# 4H-Charlieplex84.net
KiCad netlist of a schematic drawn in EAGLE
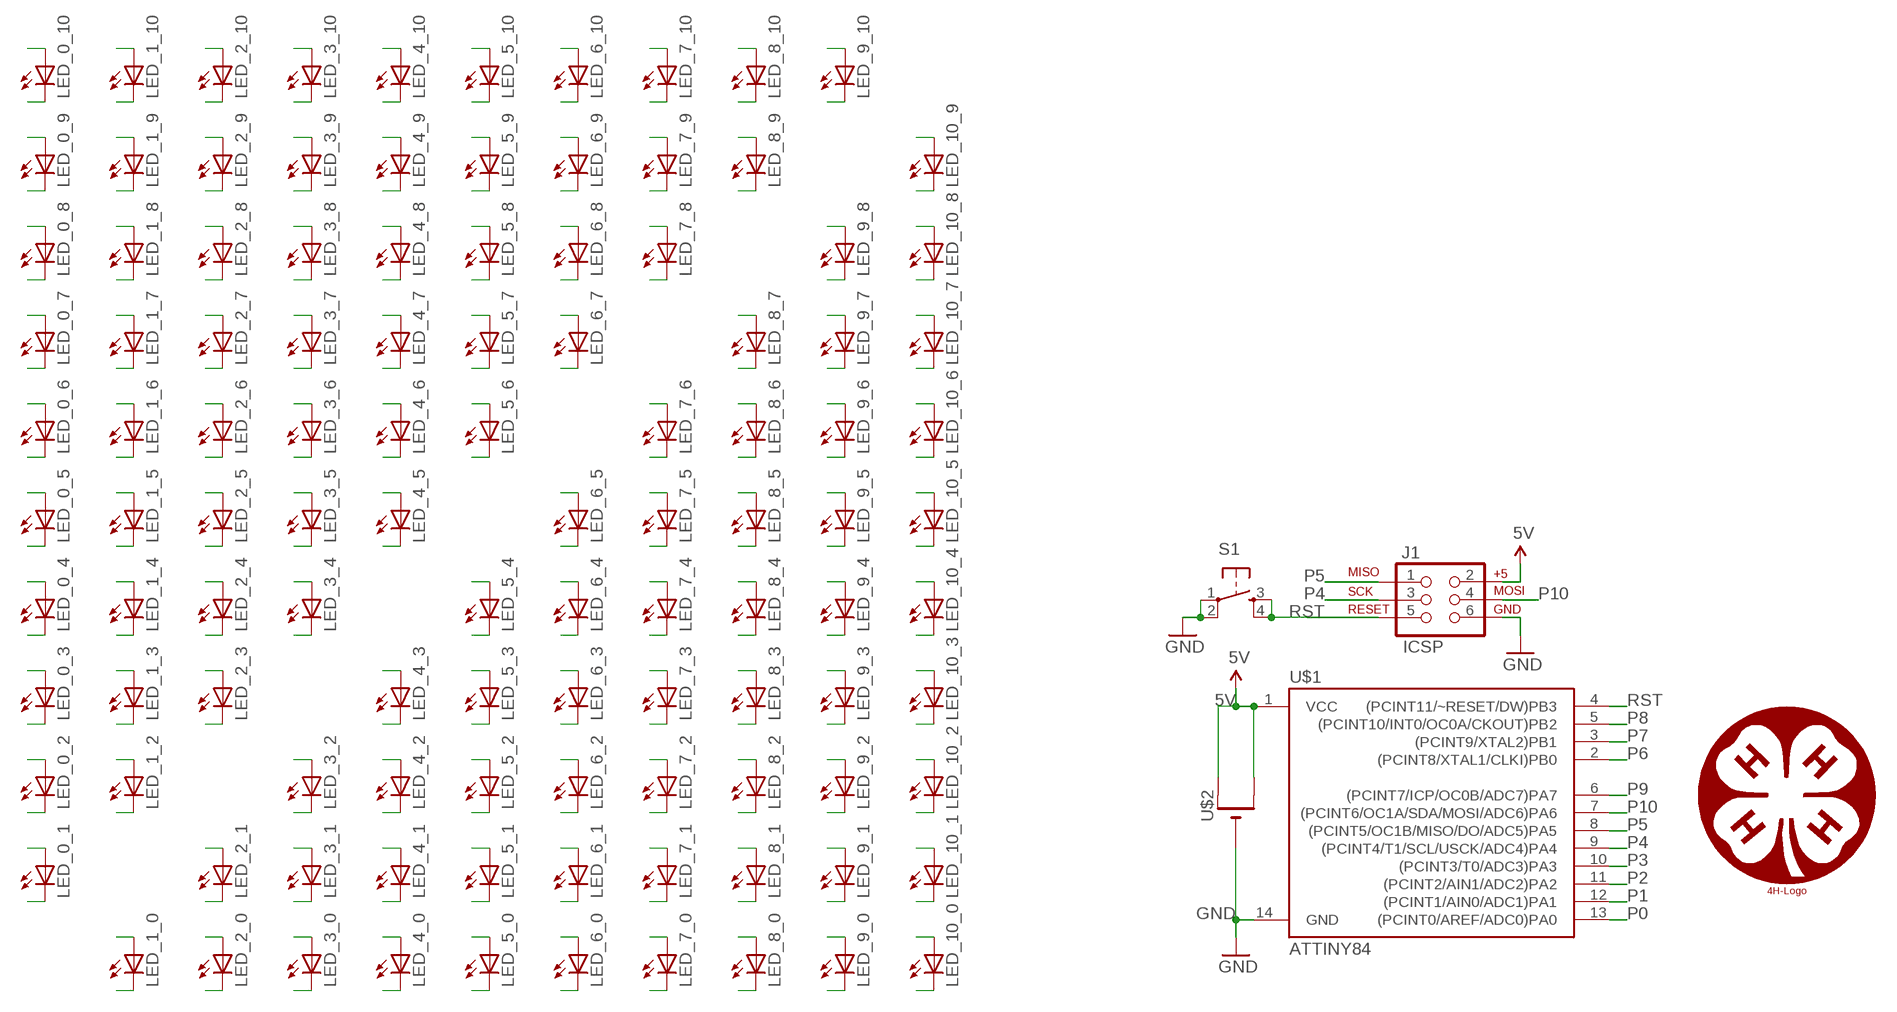
[diagram p0: schematic, sheet 1]

(export (version "E")
  (design (tool "Eeschema 10.0.6"))
  (components
    (comp (ref "J1")
      (value "ICSP")
      (footprint "eagle-import:2X3-NS")
      (libsource (lib "eagle-import") (part "AVR_SPI_PRG_6LABELED"))
    )
    (comp (ref "LED_0_1")
      (value "LEDOVAL")
      (footprint "eagle-import:LED-OVAL")
      (libsource (lib "eagle-import") (part "LEDOVAL"))
    )
    (comp (ref "LED_0_2")
      (value "LEDOVAL")
      (footprint "eagle-import:LED-OVAL")
      (libsource (lib "eagle-import") (part "LEDOVAL"))
    )
    (comp (ref "LED_0_3")
      (value "LEDOVAL")
      (footprint "eagle-import:LED-OVAL")
      (libsource (lib "eagle-import") (part "LEDOVAL"))
    )
    (comp (ref "LED_0_4")
      (value "LEDOVAL")
      (footprint "eagle-import:LED-OVAL")
      (libsource (lib "eagle-import") (part "LEDOVAL"))
    )
    (comp (ref "LED_0_5")
      (value "LEDOVAL")
      (footprint "eagle-import:LED-OVAL")
      (libsource (lib "eagle-import") (part "LEDOVAL"))
    )
    (comp (ref "LED_0_6")
      (value "LEDOVAL")
      (footprint "eagle-import:LED-OVAL")
      (libsource (lib "eagle-import") (part "LEDOVAL"))
    )
    (comp (ref "LED_0_7")
      (value "LEDOVAL")
      (footprint "eagle-import:LED-OVAL")
      (libsource (lib "eagle-import") (part "LEDOVAL"))
    )
    (comp (ref "LED_0_8")
      (value "LEDOVAL")
      (footprint "eagle-import:LED-OVAL")
      (libsource (lib "eagle-import") (part "LEDOVAL"))
    )
    (comp (ref "LED_0_9")
      (value "LEDOVAL")
      (footprint "eagle-import:LED-OVAL")
      (libsource (lib "eagle-import") (part "LEDOVAL"))
    )
    (comp (ref "LED_0_10")
      (value "LEDOVAL")
      (footprint "eagle-import:LED-OVAL")
      (libsource (lib "eagle-import") (part "LEDOVAL"))
    )
    (comp (ref "LED_1_0")
      (value "LEDOVAL")
      (footprint "eagle-import:LED-OVAL")
      (libsource (lib "eagle-import") (part "LEDOVAL"))
    )
    (comp (ref "LED_1_2")
      (value "LEDOVAL")
      (footprint "eagle-import:LED-OVAL")
      (libsource (lib "eagle-import") (part "LEDOVAL"))
    )
    (comp (ref "LED_1_3")
      (value "LEDOVAL")
      (footprint "eagle-import:LED-OVAL")
      (libsource (lib "eagle-import") (part "LEDOVAL"))
    )
    (comp (ref "LED_1_4")
      (value "LEDOVAL")
      (footprint "eagle-import:LED-OVAL")
      (libsource (lib "eagle-import") (part "LEDOVAL"))
    )
    (comp (ref "LED_1_5")
      (value "LEDOVAL")
      (footprint "eagle-import:LED-OVAL")
      (libsource (lib "eagle-import") (part "LEDOVAL"))
    )
    (comp (ref "LED_1_6")
      (value "LEDOVAL")
      (footprint "eagle-import:LED-OVAL")
      (libsource (lib "eagle-import") (part "LEDOVAL"))
    )
    (comp (ref "LED_1_7")
      (value "LEDOVAL")
      (footprint "eagle-import:LED-OVAL")
      (libsource (lib "eagle-import") (part "LEDOVAL"))
    )
    (comp (ref "LED_1_8")
      (value "LEDOVAL")
      (footprint "eagle-import:LED-OVAL")
      (libsource (lib "eagle-import") (part "LEDOVAL"))
    )
    (comp (ref "LED_1_9")
      (value "LEDOVAL")
      (footprint "eagle-import:LED-OVAL")
      (libsource (lib "eagle-import") (part "LEDOVAL"))
    )
    (comp (ref "LED_1_10")
      (value "LEDOVAL")
      (footprint "eagle-import:LED-OVAL")
      (libsource (lib "eagle-import") (part "LEDOVAL"))
    )
    (comp (ref "LED_2_0")
      (value "LEDOVAL")
      (footprint "eagle-import:LED-OVAL")
      (libsource (lib "eagle-import") (part "LEDOVAL"))
    )
    (comp (ref "LED_2_1")
      (value "LEDOVAL")
      (footprint "eagle-import:LED-OVAL")
      (libsource (lib "eagle-import") (part "LEDOVAL"))
    )
    (comp (ref "LED_2_3")
      (value "LEDOVAL")
      (footprint "eagle-import:LED-OVAL")
      (libsource (lib "eagle-import") (part "LEDOVAL"))
    )
    (comp (ref "LED_2_4")
      (value "LEDOVAL")
      (footprint "eagle-import:LED-OVAL")
      (libsource (lib "eagle-import") (part "LEDOVAL"))
    )
    (comp (ref "LED_2_5")
      (value "LEDOVAL")
      (footprint "eagle-import:LED-OVAL")
      (libsource (lib "eagle-import") (part "LEDOVAL"))
    )
    (comp (ref "LED_2_6")
      (value "LEDOVAL")
      (footprint "eagle-import:LED-OVAL")
      (libsource (lib "eagle-import") (part "LEDOVAL"))
    )
    (comp (ref "LED_2_7")
      (value "LEDOVAL")
      (footprint "eagle-import:LED-OVAL")
      (libsource (lib "eagle-import") (part "LEDOVAL"))
    )
    (comp (ref "LED_2_8")
      (value "LEDOVAL")
      (footprint "eagle-import:LED-OVAL")
      (libsource (lib "eagle-import") (part "LEDOVAL"))
    )
    (comp (ref "LED_2_9")
      (value "LEDOVAL")
      (footprint "eagle-import:LED-OVAL")
      (libsource (lib "eagle-import") (part "LEDOVAL"))
    )
    (comp (ref "LED_2_10")
      (value "LEDOVAL")
      (footprint "eagle-import:LED-OVAL")
      (libsource (lib "eagle-import") (part "LEDOVAL"))
    )
    (comp (ref "LED_3_0")
      (value "LEDOVAL")
      (footprint "eagle-import:LED-OVAL")
      (libsource (lib "eagle-import") (part "LEDOVAL"))
    )
    (comp (ref "LED_3_1")
      (value "LEDOVAL")
      (footprint "eagle-import:LED-OVAL")
      (libsource (lib "eagle-import") (part "LEDOVAL"))
    )
    (comp (ref "LED_3_2")
      (value "LEDOVAL")
      (footprint "eagle-import:LED-OVAL")
      (libsource (lib "eagle-import") (part "LEDOVAL"))
    )
    (comp (ref "LED_3_4")
      (value "LEDOVAL")
      (footprint "eagle-import:LED-OVAL")
      (libsource (lib "eagle-import") (part "LEDOVAL"))
    )
    (comp (ref "LED_3_5")
      (value "LEDOVAL")
      (footprint "eagle-import:LED-OVAL")
      (libsource (lib "eagle-import") (part "LEDOVAL"))
    )
    (comp (ref "LED_3_6")
      (value "LEDOVAL")
      (footprint "eagle-import:LED-OVAL")
      (libsource (lib "eagle-import") (part "LEDOVAL"))
    )
    (comp (ref "LED_3_7")
      (value "LEDOVAL")
      (footprint "eagle-import:LED-OVAL")
      (libsource (lib "eagle-import") (part "LEDOVAL"))
    )
    (comp (ref "LED_3_8")
      (value "LEDOVAL")
      (footprint "eagle-import:LED-OVAL")
      (libsource (lib "eagle-import") (part "LEDOVAL"))
    )
    (comp (ref "LED_3_9")
      (value "LEDOVAL")
      (footprint "eagle-import:LED-OVAL")
      (libsource (lib "eagle-import") (part "LEDOVAL"))
    )
    (comp (ref "LED_3_10")
      (value "LEDOVAL")
      (footprint "eagle-import:LED-OVAL")
      (libsource (lib "eagle-import") (part "LEDOVAL"))
    )
    (comp (ref "LED_4_0")
      (value "LEDOVAL")
      (footprint "eagle-import:LED-OVAL")
      (libsource (lib "eagle-import") (part "LEDOVAL"))
    )
    (comp (ref "LED_4_1")
      (value "LEDOVAL")
      (footprint "eagle-import:LED-OVAL")
      (libsource (lib "eagle-import") (part "LEDOVAL"))
    )
    (comp (ref "LED_4_2")
      (value "LEDOVAL")
      (footprint "eagle-import:LED-OVAL")
      (libsource (lib "eagle-import") (part "LEDOVAL"))
    )
    (comp (ref "LED_4_3")
      (value "LEDOVAL")
      (footprint "eagle-import:LED-OVAL")
      (libsource (lib "eagle-import") (part "LEDOVAL"))
    )
    (comp (ref "LED_4_5")
      (value "LEDOVAL")
      (footprint "eagle-import:LED-OVAL")
      (libsource (lib "eagle-import") (part "LEDOVAL"))
    )
    (comp (ref "LED_4_6")
      (value "LEDOVAL")
      (footprint "eagle-import:LED-OVAL")
      (libsource (lib "eagle-import") (part "LEDOVAL"))
    )
    (comp (ref "LED_4_7")
      (value "LEDOVAL")
      (footprint "eagle-import:LED-OVAL")
      (libsource (lib "eagle-import") (part "LEDOVAL"))
    )
    (comp (ref "LED_4_8")
      (value "LEDOVAL")
      (footprint "eagle-import:LED-OVAL")
      (libsource (lib "eagle-import") (part "LEDOVAL"))
    )
    (comp (ref "LED_4_9")
      (value "LEDOVAL")
      (footprint "eagle-import:LED-OVAL")
      (libsource (lib "eagle-import") (part "LEDOVAL"))
    )
    (comp (ref "LED_4_10")
      (value "LEDOVAL")
      (footprint "eagle-import:LED-OVAL")
      (libsource (lib "eagle-import") (part "LEDOVAL"))
    )
    (comp (ref "LED_5_0")
      (value "LEDOVAL")
      (footprint "eagle-import:LED-OVAL")
      (libsource (lib "eagle-import") (part "LEDOVAL"))
    )
    (comp (ref "LED_5_1")
      (value "LEDOVAL")
      (footprint "eagle-import:LED-OVAL")
      (libsource (lib "eagle-import") (part "LEDOVAL"))
    )
    (comp (ref "LED_5_2")
      (value "LEDOVAL")
      (footprint "eagle-import:LED-OVAL")
      (libsource (lib "eagle-import") (part "LEDOVAL"))
    )
    (comp (ref "LED_5_3")
      (value "LEDOVAL")
      (footprint "eagle-import:LED-OVAL")
      (libsource (lib "eagle-import") (part "LEDOVAL"))
    )
    (comp (ref "LED_5_4")
      (value "LEDOVAL")
      (footprint "eagle-import:LED-OVAL")
      (libsource (lib "eagle-import") (part "LEDOVAL"))
    )
    (comp (ref "LED_5_6")
      (value "LEDOVAL")
      (footprint "eagle-import:LED-OVAL")
      (libsource (lib "eagle-import") (part "LEDOVAL"))
    )
    (comp (ref "LED_5_7")
      (value "LEDOVAL")
      (footprint "eagle-import:LED-OVAL")
      (libsource (lib "eagle-import") (part "LEDOVAL"))
    )
    (comp (ref "LED_5_8")
      (value "LEDOVAL")
      (footprint "eagle-import:LED-OVAL")
      (libsource (lib "eagle-import") (part "LEDOVAL"))
    )
    (comp (ref "LED_5_9")
      (value "LEDOVAL")
      (footprint "eagle-import:LED-OVAL")
      (libsource (lib "eagle-import") (part "LEDOVAL"))
    )
    (comp (ref "LED_5_10")
      (value "LEDOVAL")
      (footprint "eagle-import:LED-OVAL")
      (libsource (lib "eagle-import") (part "LEDOVAL"))
    )
    (comp (ref "LED_6_0")
      (value "LEDOVAL")
      (footprint "eagle-import:LED-OVAL")
      (libsource (lib "eagle-import") (part "LEDOVAL"))
    )
    (comp (ref "LED_6_1")
      (value "LEDOVAL")
      (footprint "eagle-import:LED-OVAL")
      (libsource (lib "eagle-import") (part "LEDOVAL"))
    )
    (comp (ref "LED_6_2")
      (value "LEDOVAL")
      (footprint "eagle-import:LED-OVAL")
      (libsource (lib "eagle-import") (part "LEDOVAL"))
    )
    (comp (ref "LED_6_3")
      (value "LEDOVAL")
      (footprint "eagle-import:LED-OVAL")
      (libsource (lib "eagle-import") (part "LEDOVAL"))
    )
    (comp (ref "LED_6_4")
      (value "LEDOVAL")
      (footprint "eagle-import:LED-OVAL")
      (libsource (lib "eagle-import") (part "LEDOVAL"))
    )
    (comp (ref "LED_6_5")
      (value "LEDOVAL")
      (footprint "eagle-import:LED-OVAL")
      (libsource (lib "eagle-import") (part "LEDOVAL"))
    )
    (comp (ref "LED_6_7")
      (value "LEDOVAL")
      (footprint "eagle-import:LED-OVAL")
      (libsource (lib "eagle-import") (part "LEDOVAL"))
    )
    (comp (ref "LED_6_8")
      (value "LEDOVAL")
      (footprint "eagle-import:LED-OVAL")
      (libsource (lib "eagle-import") (part "LEDOVAL"))
    )
    (comp (ref "LED_6_9")
      (value "LEDOVAL")
      (footprint "eagle-import:LED-OVAL")
      (libsource (lib "eagle-import") (part "LEDOVAL"))
    )
    (comp (ref "LED_6_10")
      (value "LEDOVAL")
      (footprint "eagle-import:LED-OVAL")
      (libsource (lib "eagle-import") (part "LEDOVAL"))
    )
    (comp (ref "LED_7_0")
      (value "LEDOVAL")
      (footprint "eagle-import:LED-OVAL")
      (libsource (lib "eagle-import") (part "LEDOVAL"))
    )
    (comp (ref "LED_7_1")
      (value "LEDOVAL")
      (footprint "eagle-import:LED-OVAL")
      (libsource (lib "eagle-import") (part "LEDOVAL"))
    )
    (comp (ref "LED_7_2")
      (value "LEDOVAL")
      (footprint "eagle-import:LED-OVAL")
      (libsource (lib "eagle-import") (part "LEDOVAL"))
    )
    (comp (ref "LED_7_3")
      (value "LEDOVAL")
      (footprint "eagle-import:LED-OVAL")
      (libsource (lib "eagle-import") (part "LEDOVAL"))
    )
    (comp (ref "LED_7_4")
      (value "LEDOVAL")
      (footprint "eagle-import:LED-OVAL")
      (libsource (lib "eagle-import") (part "LEDOVAL"))
    )
    (comp (ref "LED_7_5")
      (value "LEDOVAL")
      (footprint "eagle-import:LED-OVAL")
      (libsource (lib "eagle-import") (part "LEDOVAL"))
    )
    (comp (ref "LED_7_6")
      (value "LEDOVAL")
      (footprint "eagle-import:LED-OVAL")
      (libsource (lib "eagle-import") (part "LEDOVAL"))
    )
    (comp (ref "LED_7_8")
      (value "LEDOVAL")
      (footprint "eagle-import:LED-OVAL")
      (libsource (lib "eagle-import") (part "LEDOVAL"))
    )
    (comp (ref "LED_7_9")
      (value "LEDOVAL")
      (footprint "eagle-import:LED-OVAL")
      (libsource (lib "eagle-import") (part "LEDOVAL"))
    )
    (comp (ref "LED_7_10")
      (value "LEDOVAL")
      (footprint "eagle-import:LED-OVAL")
      (libsource (lib "eagle-import") (part "LEDOVAL"))
    )
    (comp (ref "LED_8_0")
      (value "LEDOVAL")
      (footprint "eagle-import:LED-OVAL")
      (libsource (lib "eagle-import") (part "LEDOVAL"))
    )
    (comp (ref "LED_8_1")
      (value "LEDOVAL")
      (footprint "eagle-import:LED-OVAL")
      (libsource (lib "eagle-import") (part "LEDOVAL"))
    )
    (comp (ref "LED_8_2")
      (value "LEDOVAL")
      (footprint "eagle-import:LED-OVAL")
      (libsource (lib "eagle-import") (part "LEDOVAL"))
    )
    (comp (ref "LED_8_3")
      (value "LEDOVAL")
      (footprint "eagle-import:LED-OVAL")
      (libsource (lib "eagle-import") (part "LEDOVAL"))
    )
    (comp (ref "LED_8_4")
      (value "LEDOVAL")
      (footprint "eagle-import:LED-OVAL")
      (libsource (lib "eagle-import") (part "LEDOVAL"))
    )
    (comp (ref "LED_8_5")
      (value "LEDOVAL")
      (footprint "eagle-import:LED-OVAL")
      (libsource (lib "eagle-import") (part "LEDOVAL"))
    )
    (comp (ref "LED_8_6")
      (value "LEDOVAL")
      (footprint "eagle-import:LED-OVAL")
      (libsource (lib "eagle-import") (part "LEDOVAL"))
    )
    (comp (ref "LED_8_7")
      (value "LEDOVAL")
      (footprint "eagle-import:LED-OVAL")
      (libsource (lib "eagle-import") (part "LEDOVAL"))
    )
    (comp (ref "LED_8_9")
      (value "LEDOVAL")
      (footprint "eagle-import:LED-OVAL")
      (libsource (lib "eagle-import") (part "LEDOVAL"))
    )
    (comp (ref "LED_8_10")
      (value "LEDOVAL")
      (footprint "eagle-import:LED-OVAL")
      (libsource (lib "eagle-import") (part "LEDOVAL"))
    )
    (comp (ref "LED_9_0")
      (value "LEDOVAL")
      (footprint "eagle-import:LED-OVAL")
      (libsource (lib "eagle-import") (part "LEDOVAL"))
    )
    (comp (ref "LED_9_1")
      (value "LEDOVAL")
      (footprint "eagle-import:LED-OVAL")
      (libsource (lib "eagle-import") (part "LEDOVAL"))
    )
    (comp (ref "LED_9_2")
      (value "LEDOVAL")
      (footprint "eagle-import:LED-OVAL")
      (libsource (lib "eagle-import") (part "LEDOVAL"))
    )
    (comp (ref "LED_9_3")
      (value "LEDOVAL")
      (footprint "eagle-import:LED-OVAL")
      (libsource (lib "eagle-import") (part "LEDOVAL"))
    )
    (comp (ref "LED_9_4")
      (value "LEDOVAL")
      (footprint "eagle-import:LED-OVAL")
      (libsource (lib "eagle-import") (part "LEDOVAL"))
    )
    (comp (ref "LED_9_5")
      (value "LEDOVAL")
      (footprint "eagle-import:LED-OVAL")
      (libsource (lib "eagle-import") (part "LEDOVAL"))
    )
    (comp (ref "LED_9_6")
      (value "LEDOVAL")
      (footprint "eagle-import:LED-OVAL")
      (libsource (lib "eagle-import") (part "LEDOVAL"))
    )
    (comp (ref "LED_9_7")
      (value "LEDOVAL")
      (footprint "eagle-import:LED-OVAL")
      (libsource (lib "eagle-import") (part "LEDOVAL"))
    )
    (comp (ref "LED_9_8")
      (value "LEDOVAL")
      (footprint "eagle-import:LED-OVAL")
      (libsource (lib "eagle-import") (part "LEDOVAL"))
    )
    (comp (ref "LED_9_10")
      (value "LEDOVAL")
      (footprint "eagle-import:LED-OVAL")
      (libsource (lib "eagle-import") (part "LEDOVAL"))
    )
    (comp (ref "LED_10_0")
      (value "LEDOVAL")
      (footprint "eagle-import:LED-OVAL")
      (libsource (lib "eagle-import") (part "LEDOVAL"))
    )
    (comp (ref "LED_10_1")
      (value "LEDOVAL")
      (footprint "eagle-import:LED-OVAL")
      (libsource (lib "eagle-import") (part "LEDOVAL"))
    )
    (comp (ref "LED_10_2")
      (value "LEDOVAL")
      (footprint "eagle-import:LED-OVAL")
      (libsource (lib "eagle-import") (part "LEDOVAL"))
    )
    (comp (ref "LED_10_3")
      (value "LEDOVAL")
      (footprint "eagle-import:LED-OVAL")
      (libsource (lib "eagle-import") (part "LEDOVAL"))
    )
    (comp (ref "LED_10_4")
      (value "LEDOVAL")
      (footprint "eagle-import:LED-OVAL")
      (libsource (lib "eagle-import") (part "LEDOVAL"))
    )
    (comp (ref "LED_10_5")
      (value "LEDOVAL")
      (footprint "eagle-import:LED-OVAL")
      (libsource (lib "eagle-import") (part "LEDOVAL"))
    )
    (comp (ref "LED_10_6")
      (value "LEDOVAL")
      (footprint "eagle-import:LED-OVAL")
      (libsource (lib "eagle-import") (part "LEDOVAL"))
    )
    (comp (ref "LED_10_7")
      (value "LEDOVAL")
      (footprint "eagle-import:LED-OVAL")
      (libsource (lib "eagle-import") (part "LEDOVAL"))
    )
    (comp (ref "LED_10_8")
      (value "LEDOVAL")
      (footprint "eagle-import:LED-OVAL")
      (libsource (lib "eagle-import") (part "LEDOVAL"))
    )
    (comp (ref "LED_10_9")
      (value "LEDOVAL")
      (footprint "eagle-import:LED-OVAL")
      (libsource (lib "eagle-import") (part "LEDOVAL"))
    )
    (comp (ref "S1")
      (value "TAC_SWITCHPTH")
      (footprint "eagle-import:TACTILE-PTH")
      (libsource (lib "eagle-import") (part "TAC_SWITCHPTH"))
    )
    (comp (ref "U$1")
      (value "ATTINY84")
      (footprint "eagle-import:DIL14")
      (libsource (lib "eagle-import") (part "ATTINY84ATTINY84-20PU"))
    )
    (comp (ref "U$2")
      (value "CR2032THM")
      (footprint "eagle-import:CR2032-THRU")
      (libsource (lib "eagle-import") (part "CR2032THM"))
    )
    (comp (ref "U$3")
      (value "4H-LOGO6")
      (footprint "eagle-import:4H_LOGO_6")
      (libsource (lib "eagle-import") (part "4H-LOGO6"))
    )
  )
  (nets
    (net (code "1") (name "/P0") (class "Default")
      (node (ref "LED_0_1") (pin "CATHODE") (pinfunction "C_CATHODE") (pintype "passive"))
      (node (ref "LED_0_10") (pin "CATHODE") (pinfunction "C_CATHODE") (pintype "passive"))
      (node (ref "LED_0_2") (pin "CATHODE") (pinfunction "C_CATHODE") (pintype "passive"))
      (node (ref "LED_0_3") (pin "CATHODE") (pinfunction "C_CATHODE") (pintype "passive"))
      (node (ref "LED_0_4") (pin "CATHODE") (pinfunction "C_CATHODE") (pintype "passive"))
      (node (ref "LED_0_5") (pin "CATHODE") (pinfunction "C_CATHODE") (pintype "passive"))
      (node (ref "LED_0_6") (pin "CATHODE") (pinfunction "C_CATHODE") (pintype "passive"))
      (node (ref "LED_0_7") (pin "CATHODE") (pinfunction "C_CATHODE") (pintype "passive"))
      (node (ref "LED_0_8") (pin "CATHODE") (pinfunction "C_CATHODE") (pintype "passive"))
      (node (ref "LED_0_9") (pin "CATHODE") (pinfunction "C_CATHODE") (pintype "passive"))
      (node (ref "LED_10_0") (pin "ANODE") (pinfunction "A_ANODE") (pintype "passive"))
      (node (ref "LED_1_0") (pin "ANODE") (pinfunction "A_ANODE") (pintype "passive"))
      (node (ref "LED_2_0") (pin "ANODE") (pinfunction "A_ANODE") (pintype "passive"))
      (node (ref "LED_3_0") (pin "ANODE") (pinfunction "A_ANODE") (pintype "passive"))
      (node (ref "LED_4_0") (pin "ANODE") (pinfunction "A_ANODE") (pintype "passive"))
      (node (ref "LED_5_0") (pin "ANODE") (pinfunction "A_ANODE") (pintype "passive"))
      (node (ref "LED_6_0") (pin "ANODE") (pinfunction "A_ANODE") (pintype "passive"))
      (node (ref "LED_7_0") (pin "ANODE") (pinfunction "A_ANODE") (pintype "passive"))
      (node (ref "LED_8_0") (pin "ANODE") (pinfunction "A_ANODE") (pintype "passive"))
      (node (ref "LED_9_0") (pin "ANODE") (pinfunction "A_ANODE") (pintype "passive"))
      (node (ref "U$1") (pin "13") (pinfunction "(PCINT0/AREF/ADC0)PA0_13") (pintype "bidirectional"))
    )
    (net (code "2") (name "/P1") (class "Default")
      (node (ref "LED_0_1") (pin "ANODE") (pinfunction "A_ANODE") (pintype "passive"))
      (node (ref "LED_10_1") (pin "ANODE") (pinfunction "A_ANODE") (pintype "passive"))
      (node (ref "LED_1_0") (pin "CATHODE") (pinfunction "C_CATHODE") (pintype "passive"))
      (node (ref "LED_1_10") (pin "CATHODE") (pinfunction "C_CATHODE") (pintype "passive"))
      (node (ref "LED_1_2") (pin "CATHODE") (pinfunction "C_CATHODE") (pintype "passive"))
      (node (ref "LED_1_3") (pin "CATHODE") (pinfunction "C_CATHODE") (pintype "passive"))
      (node (ref "LED_1_4") (pin "CATHODE") (pinfunction "C_CATHODE") (pintype "passive"))
      (node (ref "LED_1_5") (pin "CATHODE") (pinfunction "C_CATHODE") (pintype "passive"))
      (node (ref "LED_1_6") (pin "CATHODE") (pinfunction "C_CATHODE") (pintype "passive"))
      (node (ref "LED_1_7") (pin "CATHODE") (pinfunction "C_CATHODE") (pintype "passive"))
      (node (ref "LED_1_8") (pin "CATHODE") (pinfunction "C_CATHODE") (pintype "passive"))
      (node (ref "LED_1_9") (pin "CATHODE") (pinfunction "C_CATHODE") (pintype "passive"))
      (node (ref "LED_2_1") (pin "ANODE") (pinfunction "A_ANODE") (pintype "passive"))
      (node (ref "LED_3_1") (pin "ANODE") (pinfunction "A_ANODE") (pintype "passive"))
      (node (ref "LED_4_1") (pin "ANODE") (pinfunction "A_ANODE") (pintype "passive"))
      (node (ref "LED_5_1") (pin "ANODE") (pinfunction "A_ANODE") (pintype "passive"))
      (node (ref "LED_6_1") (pin "ANODE") (pinfunction "A_ANODE") (pintype "passive"))
      (node (ref "LED_7_1") (pin "ANODE") (pinfunction "A_ANODE") (pintype "passive"))
      (node (ref "LED_8_1") (pin "ANODE") (pinfunction "A_ANODE") (pintype "passive"))
      (node (ref "LED_9_1") (pin "ANODE") (pinfunction "A_ANODE") (pintype "passive"))
      (node (ref "U$1") (pin "12") (pinfunction "(PCINT1/AIN0/ADC1)PA1_12") (pintype "bidirectional"))
    )
    (net (code "3") (name "/P2") (class "Default")
      (node (ref "LED_0_2") (pin "ANODE") (pinfunction "A_ANODE") (pintype "passive"))
      (node (ref "LED_10_2") (pin "ANODE") (pinfunction "A_ANODE") (pintype "passive"))
      (node (ref "LED_1_2") (pin "ANODE") (pinfunction "A_ANODE") (pintype "passive"))
      (node (ref "LED_2_0") (pin "CATHODE") (pinfunction "C_CATHODE") (pintype "passive"))
      (node (ref "LED_2_1") (pin "CATHODE") (pinfunction "C_CATHODE") (pintype "passive"))
      (node (ref "LED_2_10") (pin "CATHODE") (pinfunction "C_CATHODE") (pintype "passive"))
      (node (ref "LED_2_3") (pin "CATHODE") (pinfunction "C_CATHODE") (pintype "passive"))
      (node (ref "LED_2_4") (pin "CATHODE") (pinfunction "C_CATHODE") (pintype "passive"))
      (node (ref "LED_2_5") (pin "CATHODE") (pinfunction "C_CATHODE") (pintype "passive"))
      (node (ref "LED_2_6") (pin "CATHODE") (pinfunction "C_CATHODE") (pintype "passive"))
      (node (ref "LED_2_7") (pin "CATHODE") (pinfunction "C_CATHODE") (pintype "passive"))
      (node (ref "LED_2_8") (pin "CATHODE") (pinfunction "C_CATHODE") (pintype "passive"))
      (node (ref "LED_2_9") (pin "CATHODE") (pinfunction "C_CATHODE") (pintype "passive"))
      (node (ref "LED_3_2") (pin "ANODE") (pinfunction "A_ANODE") (pintype "passive"))
      (node (ref "LED_4_2") (pin "ANODE") (pinfunction "A_ANODE") (pintype "passive"))
      (node (ref "LED_5_2") (pin "ANODE") (pinfunction "A_ANODE") (pintype "passive"))
      (node (ref "LED_6_2") (pin "ANODE") (pinfunction "A_ANODE") (pintype "passive"))
      (node (ref "LED_7_2") (pin "ANODE") (pinfunction "A_ANODE") (pintype "passive"))
      (node (ref "LED_8_2") (pin "ANODE") (pinfunction "A_ANODE") (pintype "passive"))
      (node (ref "LED_9_2") (pin "ANODE") (pinfunction "A_ANODE") (pintype "passive"))
      (node (ref "U$1") (pin "11") (pinfunction "(PCINT2/AIN1/ADC2)PA2_11") (pintype "bidirectional"))
    )
    (net (code "4") (name "/P3") (class "Default")
      (node (ref "LED_0_3") (pin "ANODE") (pinfunction "A_ANODE") (pintype "passive"))
      (node (ref "LED_10_3") (pin "ANODE") (pinfunction "A_ANODE") (pintype "passive"))
      (node (ref "LED_1_3") (pin "ANODE") (pinfunction "A_ANODE") (pintype "passive"))
      (node (ref "LED_2_3") (pin "ANODE") (pinfunction "A_ANODE") (pintype "passive"))
      (node (ref "LED_3_0") (pin "CATHODE") (pinfunction "C_CATHODE") (pintype "passive"))
      (node (ref "LED_3_1") (pin "CATHODE") (pinfunction "C_CATHODE") (pintype "passive"))
      (node (ref "LED_3_10") (pin "CATHODE") (pinfunction "C_CATHODE") (pintype "passive"))
      (node (ref "LED_3_2") (pin "CATHODE") (pinfunction "C_CATHODE") (pintype "passive"))
      (node (ref "LED_3_4") (pin "CATHODE") (pinfunction "C_CATHODE") (pintype "passive"))
      (node (ref "LED_3_5") (pin "CATHODE") (pinfunction "C_CATHODE") (pintype "passive"))
      (node (ref "LED_3_6") (pin "CATHODE") (pinfunction "C_CATHODE") (pintype "passive"))
      (node (ref "LED_3_7") (pin "CATHODE") (pinfunction "C_CATHODE") (pintype "passive"))
      (node (ref "LED_3_8") (pin "CATHODE") (pinfunction "C_CATHODE") (pintype "passive"))
      (node (ref "LED_3_9") (pin "CATHODE") (pinfunction "C_CATHODE") (pintype "passive"))
      (node (ref "LED_4_3") (pin "ANODE") (pinfunction "A_ANODE") (pintype "passive"))
      (node (ref "LED_5_3") (pin "ANODE") (pinfunction "A_ANODE") (pintype "passive"))
      (node (ref "LED_6_3") (pin "ANODE") (pinfunction "A_ANODE") (pintype "passive"))
      (node (ref "LED_7_3") (pin "ANODE") (pinfunction "A_ANODE") (pintype "passive"))
      (node (ref "LED_8_3") (pin "ANODE") (pinfunction "A_ANODE") (pintype "passive"))
      (node (ref "LED_9_3") (pin "ANODE") (pinfunction "A_ANODE") (pintype "passive"))
      (node (ref "U$1") (pin "10") (pinfunction "(PCINT3/T0/ADC3)PA3_10") (pintype "bidirectional"))
    )
    (net (code "5") (name "/P4") (class "Default")
      (node (ref "J1") (pin "3") (pinfunction "3_3") (pintype "passive"))
      (node (ref "LED_0_4") (pin "ANODE") (pinfunction "A_ANODE") (pintype "passive"))
      (node (ref "LED_10_4") (pin "ANODE") (pinfunction "A_ANODE") (pintype "passive"))
      (node (ref "LED_1_4") (pin "ANODE") (pinfunction "A_ANODE") (pintype "passive"))
      (node (ref "LED_2_4") (pin "ANODE") (pinfunction "A_ANODE") (pintype "passive"))
      (node (ref "LED_3_4") (pin "ANODE") (pinfunction "A_ANODE") (pintype "passive"))
      (node (ref "LED_4_0") (pin "CATHODE") (pinfunction "C_CATHODE") (pintype "passive"))
      (node (ref "LED_4_1") (pin "CATHODE") (pinfunction "C_CATHODE") (pintype "passive"))
      (node (ref "LED_4_10") (pin "CATHODE") (pinfunction "C_CATHODE") (pintype "passive"))
      (node (ref "LED_4_2") (pin "CATHODE") (pinfunction "C_CATHODE") (pintype "passive"))
      (node (ref "LED_4_3") (pin "CATHODE") (pinfunction "C_CATHODE") (pintype "passive"))
      (node (ref "LED_4_5") (pin "CATHODE") (pinfunction "C_CATHODE") (pintype "passive"))
      (node (ref "LED_4_6") (pin "CATHODE") (pinfunction "C_CATHODE") (pintype "passive"))
      (node (ref "LED_4_7") (pin "CATHODE") (pinfunction "C_CATHODE") (pintype "passive"))
      (node (ref "LED_4_8") (pin "CATHODE") (pinfunction "C_CATHODE") (pintype "passive"))
      (node (ref "LED_4_9") (pin "CATHODE") (pinfunction "C_CATHODE") (pintype "passive"))
      (node (ref "LED_5_4") (pin "ANODE") (pinfunction "A_ANODE") (pintype "passive"))
      (node (ref "LED_6_4") (pin "ANODE") (pinfunction "A_ANODE") (pintype "passive"))
      (node (ref "LED_7_4") (pin "ANODE") (pinfunction "A_ANODE") (pintype "passive"))
      (node (ref "LED_8_4") (pin "ANODE") (pinfunction "A_ANODE") (pintype "passive"))
      (node (ref "LED_9_4") (pin "ANODE") (pinfunction "A_ANODE") (pintype "passive"))
      (node (ref "U$1") (pin "9") (pinfunction "(PCINT4/T1/SCL/USCK/ADC4)PA4_9") (pintype "bidirectional"))
    )
    (net (code "6") (name "/P5") (class "Default")
      (node (ref "J1") (pin "1") (pinfunction "1_1") (pintype "passive"))
      (node (ref "LED_0_5") (pin "ANODE") (pinfunction "A_ANODE") (pintype "passive"))
      (node (ref "LED_10_5") (pin "ANODE") (pinfunction "A_ANODE") (pintype "passive"))
      (node (ref "LED_1_5") (pin "ANODE") (pinfunction "A_ANODE") (pintype "passive"))
      (node (ref "LED_2_5") (pin "ANODE") (pinfunction "A_ANODE") (pintype "passive"))
      (node (ref "LED_3_5") (pin "ANODE") (pinfunction "A_ANODE") (pintype "passive"))
      (node (ref "LED_4_5") (pin "ANODE") (pinfunction "A_ANODE") (pintype "passive"))
      (node (ref "LED_5_0") (pin "CATHODE") (pinfunction "C_CATHODE") (pintype "passive"))
      (node (ref "LED_5_1") (pin "CATHODE") (pinfunction "C_CATHODE") (pintype "passive"))
      (node (ref "LED_5_10") (pin "CATHODE") (pinfunction "C_CATHODE") (pintype "passive"))
      (node (ref "LED_5_2") (pin "CATHODE") (pinfunction "C_CATHODE") (pintype "passive"))
      (node (ref "LED_5_3") (pin "CATHODE") (pinfunction "C_CATHODE") (pintype "passive"))
      (node (ref "LED_5_4") (pin "CATHODE") (pinfunction "C_CATHODE") (pintype "passive"))
      (node (ref "LED_5_6") (pin "CATHODE") (pinfunction "C_CATHODE") (pintype "passive"))
      (node (ref "LED_5_7") (pin "CATHODE") (pinfunction "C_CATHODE") (pintype "passive"))
      (node (ref "LED_5_8") (pin "CATHODE") (pinfunction "C_CATHODE") (pintype "passive"))
      (node (ref "LED_5_9") (pin "CATHODE") (pinfunction "C_CATHODE") (pintype "passive"))
      (node (ref "LED_6_5") (pin "ANODE") (pinfunction "A_ANODE") (pintype "passive"))
      (node (ref "LED_7_5") (pin "ANODE") (pinfunction "A_ANODE") (pintype "passive"))
      (node (ref "LED_8_5") (pin "ANODE") (pinfunction "A_ANODE") (pintype "passive"))
      (node (ref "LED_9_5") (pin "ANODE") (pinfunction "A_ANODE") (pintype "passive"))
      (node (ref "U$1") (pin "8") (pinfunction "(PCINT5/OC1B/MISO/DO/ADC5)PA5_8") (pintype "bidirectional"))
    )
    (net (code "7") (name "/P6") (class "Default")
      (node (ref "LED_0_6") (pin "ANODE") (pinfunction "A_ANODE") (pintype "passive"))
      (node (ref "LED_10_6") (pin "ANODE") (pinfunction "A_ANODE") (pintype "passive"))
      (node (ref "LED_1_6") (pin "ANODE") (pinfunction "A_ANODE") (pintype "passive"))
      (node (ref "LED_2_6") (pin "ANODE") (pinfunction "A_ANODE") (pintype "passive"))
      (node (ref "LED_3_6") (pin "ANODE") (pinfunction "A_ANODE") (pintype "passive"))
      (node (ref "LED_4_6") (pin "ANODE") (pinfunction "A_ANODE") (pintype "passive"))
      (node (ref "LED_5_6") (pin "ANODE") (pinfunction "A_ANODE") (pintype "passive"))
      (node (ref "LED_6_0") (pin "CATHODE") (pinfunction "C_CATHODE") (pintype "passive"))
      (node (ref "LED_6_1") (pin "CATHODE") (pinfunction "C_CATHODE") (pintype "passive"))
      (node (ref "LED_6_10") (pin "CATHODE") (pinfunction "C_CATHODE") (pintype "passive"))
      (node (ref "LED_6_2") (pin "CATHODE") (pinfunction "C_CATHODE") (pintype "passive"))
      (node (ref "LED_6_3") (pin "CATHODE") (pinfunction "C_CATHODE") (pintype "passive"))
      (node (ref "LED_6_4") (pin "CATHODE") (pinfunction "C_CATHODE") (pintype "passive"))
      (node (ref "LED_6_5") (pin "CATHODE") (pinfunction "C_CATHODE") (pintype "passive"))
      (node (ref "LED_6_7") (pin "CATHODE") (pinfunction "C_CATHODE") (pintype "passive"))
      (node (ref "LED_6_8") (pin "CATHODE") (pinfunction "C_CATHODE") (pintype "passive"))
      (node (ref "LED_6_9") (pin "CATHODE") (pinfunction "C_CATHODE") (pintype "passive"))
      (node (ref "LED_7_6") (pin "ANODE") (pinfunction "A_ANODE") (pintype "passive"))
      (node (ref "LED_8_6") (pin "ANODE") (pinfunction "A_ANODE") (pintype "passive"))
      (node (ref "LED_9_6") (pin "ANODE") (pinfunction "A_ANODE") (pintype "passive"))
      (node (ref "U$1") (pin "2") (pinfunction "(PCINT8/XTAL1/CLKI)PB0_2") (pintype "bidirectional"))
    )
    (net (code "8") (name "/P7") (class "Default")
      (node (ref "LED_0_7") (pin "ANODE") (pinfunction "A_ANODE") (pintype "passive"))
      (node (ref "LED_10_7") (pin "ANODE") (pinfunction "A_ANODE") (pintype "passive"))
      (node (ref "LED_1_7") (pin "ANODE") (pinfunction "A_ANODE") (pintype "passive"))
      (node (ref "LED_2_7") (pin "ANODE") (pinfunction "A_ANODE") (pintype "passive"))
      (node (ref "LED_3_7") (pin "ANODE") (pinfunction "A_ANODE") (pintype "passive"))
      (node (ref "LED_4_7") (pin "ANODE") (pinfunction "A_ANODE") (pintype "passive"))
      (node (ref "LED_5_7") (pin "ANODE") (pinfunction "A_ANODE") (pintype "passive"))
      (node (ref "LED_6_7") (pin "ANODE") (pinfunction "A_ANODE") (pintype "passive"))
      (node (ref "LED_7_0") (pin "CATHODE") (pinfunction "C_CATHODE") (pintype "passive"))
      (node (ref "LED_7_1") (pin "CATHODE") (pinfunction "C_CATHODE") (pintype "passive"))
      (node (ref "LED_7_10") (pin "CATHODE") (pinfunction "C_CATHODE") (pintype "passive"))
      (node (ref "LED_7_2") (pin "CATHODE") (pinfunction "C_CATHODE") (pintype "passive"))
      (node (ref "LED_7_3") (pin "CATHODE") (pinfunction "C_CATHODE") (pintype "passive"))
      (node (ref "LED_7_4") (pin "CATHODE") (pinfunction "C_CATHODE") (pintype "passive"))
      (node (ref "LED_7_5") (pin "CATHODE") (pinfunction "C_CATHODE") (pintype "passive"))
      (node (ref "LED_7_6") (pin "CATHODE") (pinfunction "C_CATHODE") (pintype "passive"))
      (node (ref "LED_7_8") (pin "CATHODE") (pinfunction "C_CATHODE") (pintype "passive"))
      (node (ref "LED_7_9") (pin "CATHODE") (pinfunction "C_CATHODE") (pintype "passive"))
      (node (ref "LED_8_7") (pin "ANODE") (pinfunction "A_ANODE") (pintype "passive"))
      (node (ref "LED_9_7") (pin "ANODE") (pinfunction "A_ANODE") (pintype "passive"))
      (node (ref "U$1") (pin "3") (pinfunction "(PCINT9/XTAL2)PB1_3") (pintype "bidirectional"))
    )
    (net (code "9") (name "/P8") (class "Default")
      (node (ref "LED_0_8") (pin "ANODE") (pinfunction "A_ANODE") (pintype "passive"))
      (node (ref "LED_10_8") (pin "ANODE") (pinfunction "A_ANODE") (pintype "passive"))
      (node (ref "LED_1_8") (pin "ANODE") (pinfunction "A_ANODE") (pintype "passive"))
      (node (ref "LED_2_8") (pin "ANODE") (pinfunction "A_ANODE") (pintype "passive"))
      (node (ref "LED_3_8") (pin "ANODE") (pinfunction "A_ANODE") (pintype "passive"))
      (node (ref "LED_4_8") (pin "ANODE") (pinfunction "A_ANODE") (pintype "passive"))
      (node (ref "LED_5_8") (pin "ANODE") (pinfunction "A_ANODE") (pintype "passive"))
      (node (ref "LED_6_8") (pin "ANODE") (pinfunction "A_ANODE") (pintype "passive"))
      (node (ref "LED_7_8") (pin "ANODE") (pinfunction "A_ANODE") (pintype "passive"))
      (node (ref "LED_8_0") (pin "CATHODE") (pinfunction "C_CATHODE") (pintype "passive"))
      (node (ref "LED_8_1") (pin "CATHODE") (pinfunction "C_CATHODE") (pintype "passive"))
      (node (ref "LED_8_10") (pin "CATHODE") (pinfunction "C_CATHODE") (pintype "passive"))
      (node (ref "LED_8_2") (pin "CATHODE") (pinfunction "C_CATHODE") (pintype "passive"))
      (node (ref "LED_8_3") (pin "CATHODE") (pinfunction "C_CATHODE") (pintype "passive"))
      (node (ref "LED_8_4") (pin "CATHODE") (pinfunction "C_CATHODE") (pintype "passive"))
      (node (ref "LED_8_5") (pin "CATHODE") (pinfunction "C_CATHODE") (pintype "passive"))
      (node (ref "LED_8_6") (pin "CATHODE") (pinfunction "C_CATHODE") (pintype "passive"))
      (node (ref "LED_8_7") (pin "CATHODE") (pinfunction "C_CATHODE") (pintype "passive"))
      (node (ref "LED_8_9") (pin "CATHODE") (pinfunction "C_CATHODE") (pintype "passive"))
      (node (ref "LED_9_8") (pin "ANODE") (pinfunction "A_ANODE") (pintype "passive"))
      (node (ref "U$1") (pin "5") (pinfunction "(PCINT10/INT0/OC0A/CKOUT)PB2_5") (pintype "bidirectional"))
    )
    (net (code "10") (name "/P9") (class "Default")
      (node (ref "LED_0_9") (pin "ANODE") (pinfunction "A_ANODE") (pintype "passive"))
      (node (ref "LED_10_9") (pin "ANODE") (pinfunction "A_ANODE") (pintype "passive"))
      (node (ref "LED_1_9") (pin "ANODE") (pinfunction "A_ANODE") (pintype "passive"))
      (node (ref "LED_2_9") (pin "ANODE") (pinfunction "A_ANODE") (pintype "passive"))
      (node (ref "LED_3_9") (pin "ANODE") (pinfunction "A_ANODE") (pintype "passive"))
      (node (ref "LED_4_9") (pin "ANODE") (pinfunction "A_ANODE") (pintype "passive"))
      (node (ref "LED_5_9") (pin "ANODE") (pinfunction "A_ANODE") (pintype "passive"))
      (node (ref "LED_6_9") (pin "ANODE") (pinfunction "A_ANODE") (pintype "passive"))
      (node (ref "LED_7_9") (pin "ANODE") (pinfunction "A_ANODE") (pintype "passive"))
      (node (ref "LED_8_9") (pin "ANODE") (pinfunction "A_ANODE") (pintype "passive"))
      (node (ref "LED_9_0") (pin "CATHODE") (pinfunction "C_CATHODE") (pintype "passive"))
      (node (ref "LED_9_1") (pin "CATHODE") (pinfunction "C_CATHODE") (pintype "passive"))
      (node (ref "LED_9_10") (pin "CATHODE") (pinfunction "C_CATHODE") (pintype "passive"))
      (node (ref "LED_9_2") (pin "CATHODE") (pinfunction "C_CATHODE") (pintype "passive"))
      (node (ref "LED_9_3") (pin "CATHODE") (pinfunction "C_CATHODE") (pintype "passive"))
      (node (ref "LED_9_4") (pin "CATHODE") (pinfunction "C_CATHODE") (pintype "passive"))
      (node (ref "LED_9_5") (pin "CATHODE") (pinfunction "C_CATHODE") (pintype "passive"))
      (node (ref "LED_9_6") (pin "CATHODE") (pinfunction "C_CATHODE") (pintype "passive"))
      (node (ref "LED_9_7") (pin "CATHODE") (pinfunction "C_CATHODE") (pintype "passive"))
      (node (ref "LED_9_8") (pin "CATHODE") (pinfunction "C_CATHODE") (pintype "passive"))
      (node (ref "U$1") (pin "6") (pinfunction "(PCINT7/ICP/OC0B/ADC7)PA7_6") (pintype "bidirectional"))
    )
    (net (code "11") (name "/P10") (class "Default")
      (node (ref "J1") (pin "4") (pinfunction "4_4") (pintype "passive"))
      (node (ref "LED_0_10") (pin "ANODE") (pinfunction "A_ANODE") (pintype "passive"))
      (node (ref "LED_10_0") (pin "CATHODE") (pinfunction "C_CATHODE") (pintype "passive"))
      (node (ref "LED_10_1") (pin "CATHODE") (pinfunction "C_CATHODE") (pintype "passive"))
      (node (ref "LED_10_2") (pin "CATHODE") (pinfunction "C_CATHODE") (pintype "passive"))
      (node (ref "LED_10_3") (pin "CATHODE") (pinfunction "C_CATHODE") (pintype "passive"))
      (node (ref "LED_10_4") (pin "CATHODE") (pinfunction "C_CATHODE") (pintype "passive"))
      (node (ref "LED_10_5") (pin "CATHODE") (pinfunction "C_CATHODE") (pintype "passive"))
      (node (ref "LED_10_6") (pin "CATHODE") (pinfunction "C_CATHODE") (pintype "passive"))
      (node (ref "LED_10_7") (pin "CATHODE") (pinfunction "C_CATHODE") (pintype "passive"))
      (node (ref "LED_10_8") (pin "CATHODE") (pinfunction "C_CATHODE") (pintype "passive"))
      (node (ref "LED_10_9") (pin "CATHODE") (pinfunction "C_CATHODE") (pintype "passive"))
      (node (ref "LED_1_10") (pin "ANODE") (pinfunction "A_ANODE") (pintype "passive"))
      (node (ref "LED_2_10") (pin "ANODE") (pinfunction "A_ANODE") (pintype "passive"))
      (node (ref "LED_3_10") (pin "ANODE") (pinfunction "A_ANODE") (pintype "passive"))
      (node (ref "LED_4_10") (pin "ANODE") (pinfunction "A_ANODE") (pintype "passive"))
      (node (ref "LED_5_10") (pin "ANODE") (pinfunction "A_ANODE") (pintype "passive"))
      (node (ref "LED_6_10") (pin "ANODE") (pinfunction "A_ANODE") (pintype "passive"))
      (node (ref "LED_7_10") (pin "ANODE") (pinfunction "A_ANODE") (pintype "passive"))
      (node (ref "LED_8_10") (pin "ANODE") (pinfunction "A_ANODE") (pintype "passive"))
      (node (ref "LED_9_10") (pin "ANODE") (pinfunction "A_ANODE") (pintype "passive"))
      (node (ref "U$1") (pin "7") (pinfunction "(PCINT6/OC1A/SDA/MOSI/ADC6)PA6_7") (pintype "bidirectional"))
    )
    (net (code "12") (name "/RST") (class "Default")
      (node (ref "J1") (pin "5") (pinfunction "5_5") (pintype "passive"))
      (node (ref "S1") (pin "3") (pinfunction "3_3") (pintype "passive"))
      (node (ref "S1") (pin "4") (pinfunction "4_4") (pintype "passive"))
      (node (ref "U$1") (pin "4") (pinfunction "(PCINT11/~{RESET/DW})PB3_4") (pintype "bidirectional"))
    )
    (net (code "13") (name "5V") (class "Default")
      (node (ref "J1") (pin "2") (pinfunction "2_2") (pintype "passive"))
      (node (ref "U$1") (pin "1") (pinfunction "VCC_1") (pintype "bidirectional"))
      (node (ref "U$2") (pin "+1") (pinfunction "+_+1") (pintype "passive"))
      (node (ref "U$2") (pin "+2") (pinfunction "+1_+2") (pintype "passive"))
    )
    (net (code "14") (name "GND") (class "Default")
      (node (ref "J1") (pin "6") (pinfunction "6_6") (pintype "passive"))
      (node (ref "S1") (pin "1") (pinfunction "1_1") (pintype "passive"))
      (node (ref "S1") (pin "2") (pinfunction "2_2") (pintype "passive"))
      (node (ref "U$1") (pin "14") (pinfunction "GND_14") (pintype "bidirectional"))
      (node (ref "U$2") (pin "-") (pinfunction "-_-") (pintype "passive"))
    )
  )
)
